# eBox_4G_REG.net
KiCad netlist of a schematic drawn in Altium Designer
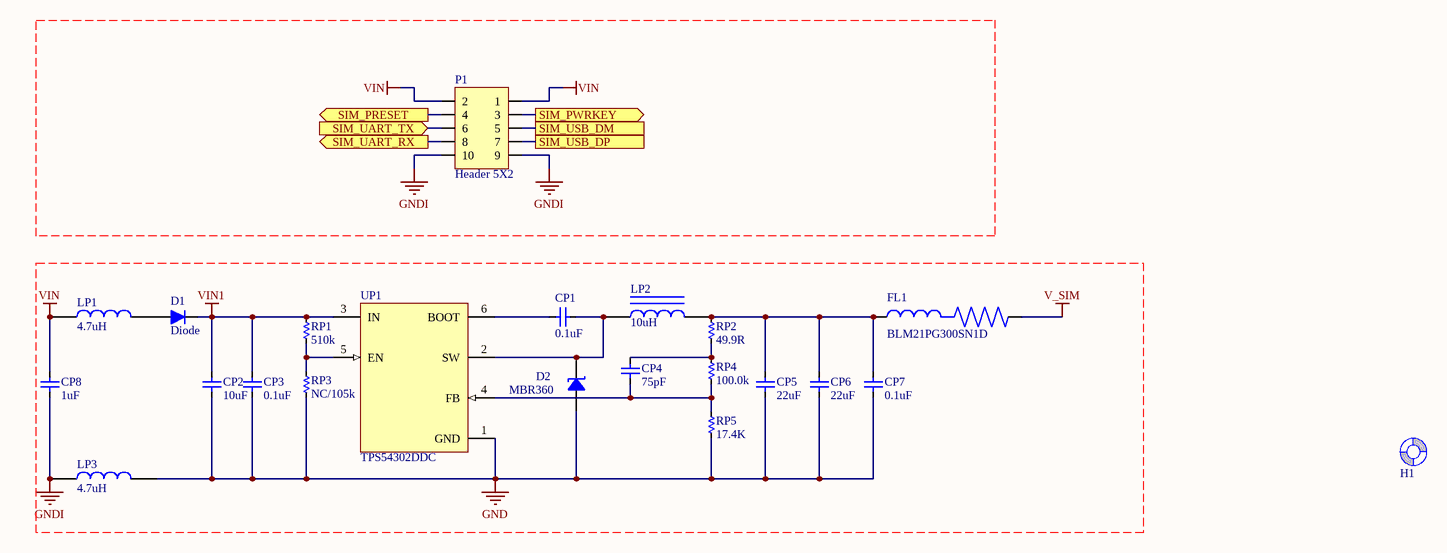
[diagram p0: eBox_4G_REG.schdoc]

(export (version "E")
  (design (tool "Eeschema 10.0.6"))
  (components
    (comp (ref "CP1")
      (value "0.1uF")
      (footprint "CC 0603")
      (description "CAP CER 0.1UF 16V X7R 0603")
      (fields
        (field (name "MANUFACTURER") "Murata Electronics")
        (field (name "MANUFACTURER PART NUMBER") "GCJ188R71C104KA01D")
      )
      (libsource (lib "car_logger_libs") (part "Capacitor NP"))
    )
    (comp (ref "CP2")
      (value "10uF")
      (footprint "CC 0805")
      (description "CAP CER 10UF 25V X5R 0805")
      (fields
        (field (name "MANUFACTURER") "Murata Electronics")
        (field (name "MANUFACTURER PART NUMBER") "GRM21BR61E106MA73L")
      )
      (libsource (lib "car_logger_libs") (part "Capacitor NP"))
    )
    (comp (ref "CP3")
      (value "0.1uF")
      (footprint "CC 0603")
      (description "CAP CER 0.1UF 16V X7R 0603")
      (fields
        (field (name "MANUFACTURER") "Murata Electronics")
        (field (name "MANUFACTURER PART NUMBER") "GCJ188R71C104KA01D")
      )
      (libsource (lib "car_logger_libs") (part "Capacitor NP"))
    )
    (comp (ref "CP4")
      (value "75pF")
      (footprint "CC 0603")
      (description "CAP CER 75PF 50V C0G/NP0 0603")
      (fields
        (field (name "MANUFACTURER") "Murata Electronics")
        (field (name "MANUFACTURER PART NUMBER") "GRM1885C1H750JA01D")
      )
      (libsource (lib "car_logger_libs") (part "Capacitor NP"))
    )
    (comp (ref "CP5")
      (value "22uF")
      (footprint "CC 0805")
      (description "CAP CER 22UF 25V X5R 0805")
      (fields
        (field (name "MANUFACTURER") "Murata Electronics")
        (field (name "MANUFACTURER PART NUMBER") "GRM21BR61E226ME44L")
      )
      (libsource (lib "car_logger_libs") (part "Capacitor NP"))
    )
    (comp (ref "CP6")
      (value "22uF")
      (footprint "CC 0805")
      (description "CAP CER 22UF 25V X5R 0805")
      (fields
        (field (name "MANUFACTURER") "Murata Electronics")
        (field (name "MANUFACTURER PART NUMBER") "GRM21BR61E226ME44L")
      )
      (libsource (lib "car_logger_libs") (part "Capacitor NP"))
    )
    (comp (ref "CP7")
      (value "0.1uF")
      (footprint "CC 0603")
      (description "CAP CER 0.1UF 16V X7R 0603")
      (fields
        (field (name "MANUFACTURER") "Murata Electronics")
        (field (name "MANUFACTURER PART NUMBER") "GCJ188R71C104KA01D")
      )
      (libsource (lib "car_logger_libs") (part "Capacitor NP"))
    )
    (comp (ref "CP8")
      (value "1uF")
      (footprint "CC 0805")
      (description "CAP CER 10UF 25V X5R 0805")
      (fields
        (field (name "MANUFACTURER") "Murata Electronics")
        (field (name "MANUFACTURER PART NUMBER") "GRM21BR61E106MA73L")
      )
      (libsource (lib "car_logger_libs") (part "Capacitor NP"))
    )
    (comp (ref "D1")
      (value "Diode")
      (footprint "DO-214AC (SMA) L")
      (description "Default Diode")
      (libsource (lib "chipfc_altium_libs") (part "Diode"))
    )
    (comp (ref "D2")
      (value "MBR360")
      (footprint "SMF DO-219AB")
      (description "TVS DIODE 57.6V 98V DO219AB")
      (fields
        (field (name "PART NUMBER") "VTVS58ASMF-HM3-08")
        (field (name "MANUFACTURER") "Vishay Semiconductor Diodes Division")
      )
      (libsource (lib "Celestial Altium Library - altium_library") (part "DIODE TVS UNI"))
    )
    (comp (ref "FL1")
      (value "BLM21PG300SN1D")
      (footprint "L 0805 (2012)")
      (description "30 Ohms @ 100MHz 1 Power Line Ferrite Bead 0805 _2012 Metric_ 4A 14mOhm")
      (fields (field (name "DIGI-KEY_PART_NUMBER") "490-1052-1-ND") (field (name "MF") "Murata"))
      (libsource (lib "BLM21PG300SN1D") (part "BLM21PG300SN1D"))
    )
    (comp (ref "H1")
      (value "Screw Hole")
      (footprint "SCREW/2.8M/5M")
      (libsource (lib "chipfc_altium_libs_extras") (part "Screw Hole"))
    )
    (comp (ref "LP1") (value "4.7uH") (footprint "0805") (libsource (lib "AltiumOpenLibs") (part "Inductor")))
    (comp (ref "LP2")
      (value "10uH")
      (footprint "IND_MWSA0518_525418")
      (description "Fixed Inductors 10uH 20% Low Profile")
      (fields
        (field (name "MANUFACTURER") "Sunlord")
        (field (name "MANUFACTURER PART NUMBER") "MWSA0518-100MT")
      )
      (libsource (lib "car_logger_libs") (part "Inductor Power"))
    )
    (comp (ref "LP3") (value "4.7uH") (footprint "0805") (libsource (lib "AltiumOpenLibs") (part "Inductor")))
    (comp (ref "P1")
      (value "Header 5X2")
      (footprint "HDR/Header/10/DL")
      (description "Header, 5-Pin, Dual row")
      (libsource (lib "chipfc_altium_libs") (part "Header 5X2"))
    )
    (comp (ref "RP1")
      (value "510k")
      (footprint "RR 0603")
      (description "RES SMD 510K OHM 1% 1/10W 0603")
      (fields
        (field (name "MANUFACTURER") "Panasonic Industrial Devices")
        (field (name "MANUFACTURER PART NUMBER") "ERJ-3EKF5103V")
      )
      (libsource (lib "car_logger_libs") (part "Resistors"))
    )
    (comp (ref "RP2")
      (value "49.9R")
      (footprint "RR 0603")
      (description "RES SMD 49.9 OHM 1% 1/10W 0603")
      (fields
        (field (name "MANUFACTURER") "Panasonic Industrial Devices")
        (field (name "MANUFACTURER PART NUMBER") "ERJ-3EKF49R9V")
      )
      (libsource (lib "car_logger_libs") (part "Resistors"))
    )
    (comp (ref "RP3")
      (value "NC/105k")
      (footprint "RR 0603")
      (description "RES SMD 105K OHM 1% 1/10W 0603")
      (fields
        (field (name "MANUFACTURER") "Panasonic Industrial Devices")
        (field (name "MANUFACTURER PART NUMBER") "ERJ-3EKF1053V")
      )
      (libsource (lib "car_logger_libs") (part "Resistors"))
    )
    (comp (ref "RP4")
      (value "100.0k")
      (footprint "RR 0603")
      (description "RES SMD 100K OHM 1% 1/10W 0603")
      (fields
        (field (name "MANUFACTURER") "Panasonic Industrial Devices")
        (field (name "MANUFACTURER PART NUMBER") "ERJ-3EKF1003V")
      )
      (libsource (lib "car_logger_libs") (part "Resistors"))
    )
    (comp (ref "RP5")
      (value "17.4K")
      (footprint "RR 0603")
      (description "RES SMD 17.4K OHM 1% 1/10W 0603")
      (fields
        (field (name "MANUFACTURER") "Panasonic Industrial Devices")
        (field (name "MANUFACTURER PART NUMBER") "ERJ-3EKF1742V")
      )
      (libsource (lib "car_logger_libs") (part "Resistors"))
    )
    (comp (ref "UP1")
      (value "TPS54302DDC")
      (footprint "SOT-23-6")
      (description "IC REG BUCK ADJ 3A TSOT23-6")
      (fields
        (field (name "MANUFACTURER") "Texas Instruments")
        (field (name "MANUFACTURER PART NUMBER") "TPS54302DDCR")
      )
      (libsource (lib "car_logger_libs") (part "TPS56339"))
    )
  )
  (nets
    (net (code "1") (name "/SIM_PRESET") (class "Default")
      (node (ref "P1") (pin "4") (pinfunction "4_4") (pintype "passive"))
    )
    (net (code "2") (name "/SIM_PWRKEY") (class "Default")
      (node (ref "P1") (pin "3") (pinfunction "3_3") (pintype "passive"))
    )
    (net (code "3") (name "/SIM_UART_RX") (class "Default")
      (node (ref "P1") (pin "8") (pinfunction "8_8") (pintype "passive"))
    )
    (net (code "4") (name "/SIM_UART_TX") (class "Default")
      (node (ref "P1") (pin "6") (pinfunction "6_6") (pintype "passive"))
    )
    (net (code "5") (name "/SIM_USB_DM") (class "Default")
      (node (ref "P1") (pin "5") (pinfunction "5_5") (pintype "passive"))
    )
    (net (code "6") (name "/SIM_USB_DP") (class "Default")
      (node (ref "P1") (pin "7") (pinfunction "7_7") (pintype "passive"))
    )
    (net (code "7") (name "GND") (class "Default")
      (node (ref "CP2") (pin "2") (pinfunction "2_2") (pintype "passive"))
      (node (ref "CP3") (pin "2") (pinfunction "2_2") (pintype "passive"))
      (node (ref "CP5") (pin "2") (pinfunction "2_2") (pintype "passive"))
      (node (ref "CP6") (pin "2") (pinfunction "2_2") (pintype "passive"))
      (node (ref "CP7") (pin "2") (pinfunction "2_2") (pintype "passive"))
      (node (ref "D2") (pin "1") (pinfunction "1_1") (pintype "passive"))
      (node (ref "LP3") (pin "2") (pinfunction "2_2") (pintype "passive"))
      (node (ref "RP3") (pin "1") (pinfunction "1_1") (pintype "passive"))
      (node (ref "RP5") (pin "2") (pinfunction "2_2") (pintype "passive"))
      (node (ref "UP1") (pin "1") (pinfunction "GND_1") (pintype "power_in"))
    )
    (net (code "8") (name "GNDI") (class "Default")
      (node (ref "CP8") (pin "2") (pinfunction "2_2") (pintype "passive"))
      (node (ref "LP3") (pin "1") (pinfunction "1_1") (pintype "passive"))
      (node (ref "P1") (pin "10") (pinfunction "10_10") (pintype "passive"))
      (node (ref "P1") (pin "9") (pinfunction "9_9") (pintype "passive"))
    )
    (net (code "9") (name "Net-(CP4-Pad1)") (class "Default")
      (node (ref "CP4") (pin "1") (pinfunction "1_1") (pintype "passive"))
      (node (ref "RP2") (pin "2") (pinfunction "2_2") (pintype "passive"))
      (node (ref "RP4") (pin "1") (pinfunction "1_1") (pintype "passive"))
    )
    (net (code "10") (name "Net-(CP5-Pad1)") (class "Default")
      (node (ref "CP5") (pin "1") (pinfunction "1_1") (pintype "passive"))
      (node (ref "CP6") (pin "1") (pinfunction "1_1") (pintype "passive"))
      (node (ref "CP7") (pin "1") (pinfunction "1_1") (pintype "passive"))
      (node (ref "FL1") (pin "1") (pinfunction "1_1") (pintype "passive"))
      (node (ref "LP2") (pin "2") (pinfunction "2_2") (pintype "passive"))
      (node (ref "RP2") (pin "1") (pinfunction "1_1") (pintype "passive"))
    )
    (net (code "11") (name "Net-(D1-A)") (class "Default")
      (node (ref "D1") (pin "1") (pinfunction "A_1") (pintype "passive"))
      (node (ref "LP1") (pin "2") (pinfunction "2_2") (pintype "passive"))
    )
    (net (code "12") (name "Net-(UP1-BOOT)") (class "Default")
      (node (ref "CP1") (pin "1") (pinfunction "1_1") (pintype "passive"))
      (node (ref "UP1") (pin "6") (pinfunction "BOOT_6") (pintype "passive"))
    )
    (net (code "13") (name "Net-(UP1-EN)") (class "Default")
      (node (ref "RP1") (pin "1") (pinfunction "1_1") (pintype "passive"))
      (node (ref "RP3") (pin "2") (pinfunction "2_2") (pintype "passive"))
      (node (ref "UP1") (pin "5") (pinfunction "EN_5") (pintype "input"))
    )
    (net (code "14") (name "Net-(UP1-FB)") (class "Default")
      (node (ref "CP4") (pin "2") (pinfunction "2_2") (pintype "passive"))
      (node (ref "RP4") (pin "2") (pinfunction "2_2") (pintype "passive"))
      (node (ref "RP5") (pin "1") (pinfunction "1_1") (pintype "passive"))
      (node (ref "UP1") (pin "4") (pinfunction "FB_4") (pintype "input"))
    )
    (net (code "15") (name "Net-(UP1-SW)") (class "Default")
      (node (ref "CP1") (pin "2") (pinfunction "2_2") (pintype "passive"))
      (node (ref "D2") (pin "2") (pinfunction "2_2") (pintype "passive"))
      (node (ref "LP2") (pin "1") (pinfunction "1_1") (pintype "passive"))
      (node (ref "UP1") (pin "2") (pinfunction "SW_2") (pintype "power_in"))
    )
    (net (code "16") (name "VIN") (class "Default")
      (node (ref "CP8") (pin "1") (pinfunction "1_1") (pintype "passive"))
      (node (ref "LP1") (pin "1") (pinfunction "1_1") (pintype "passive"))
      (node (ref "P1") (pin "1") (pinfunction "1_1") (pintype "passive"))
      (node (ref "P1") (pin "2") (pinfunction "2_2") (pintype "passive"))
    )
    (net (code "17") (name "VIN1") (class "Default")
      (node (ref "CP2") (pin "1") (pinfunction "1_1") (pintype "passive"))
      (node (ref "CP3") (pin "1") (pinfunction "1_1") (pintype "passive"))
      (node (ref "D1") (pin "2") (pinfunction "K_2") (pintype "passive"))
      (node (ref "RP1") (pin "2") (pinfunction "2_2") (pintype "passive"))
      (node (ref "UP1") (pin "3") (pinfunction "IN_3") (pintype "power_in"))
    )
    (net (code "18") (name "V_SIM") (class "Default")
      (node (ref "FL1") (pin "2") (pinfunction "2_2") (pintype "passive"))
    )
    (net (code "19") (name "unconnected-(H1-Screw-Pad1)") (class "Default")
      (node (ref "H1") (pin "1") (pinfunction "Screw_1") (pintype "passive"))
    )
  )
)
